# Power_Board_Mk_4.net
KiCad netlist of a schematic drawn in EAGLE
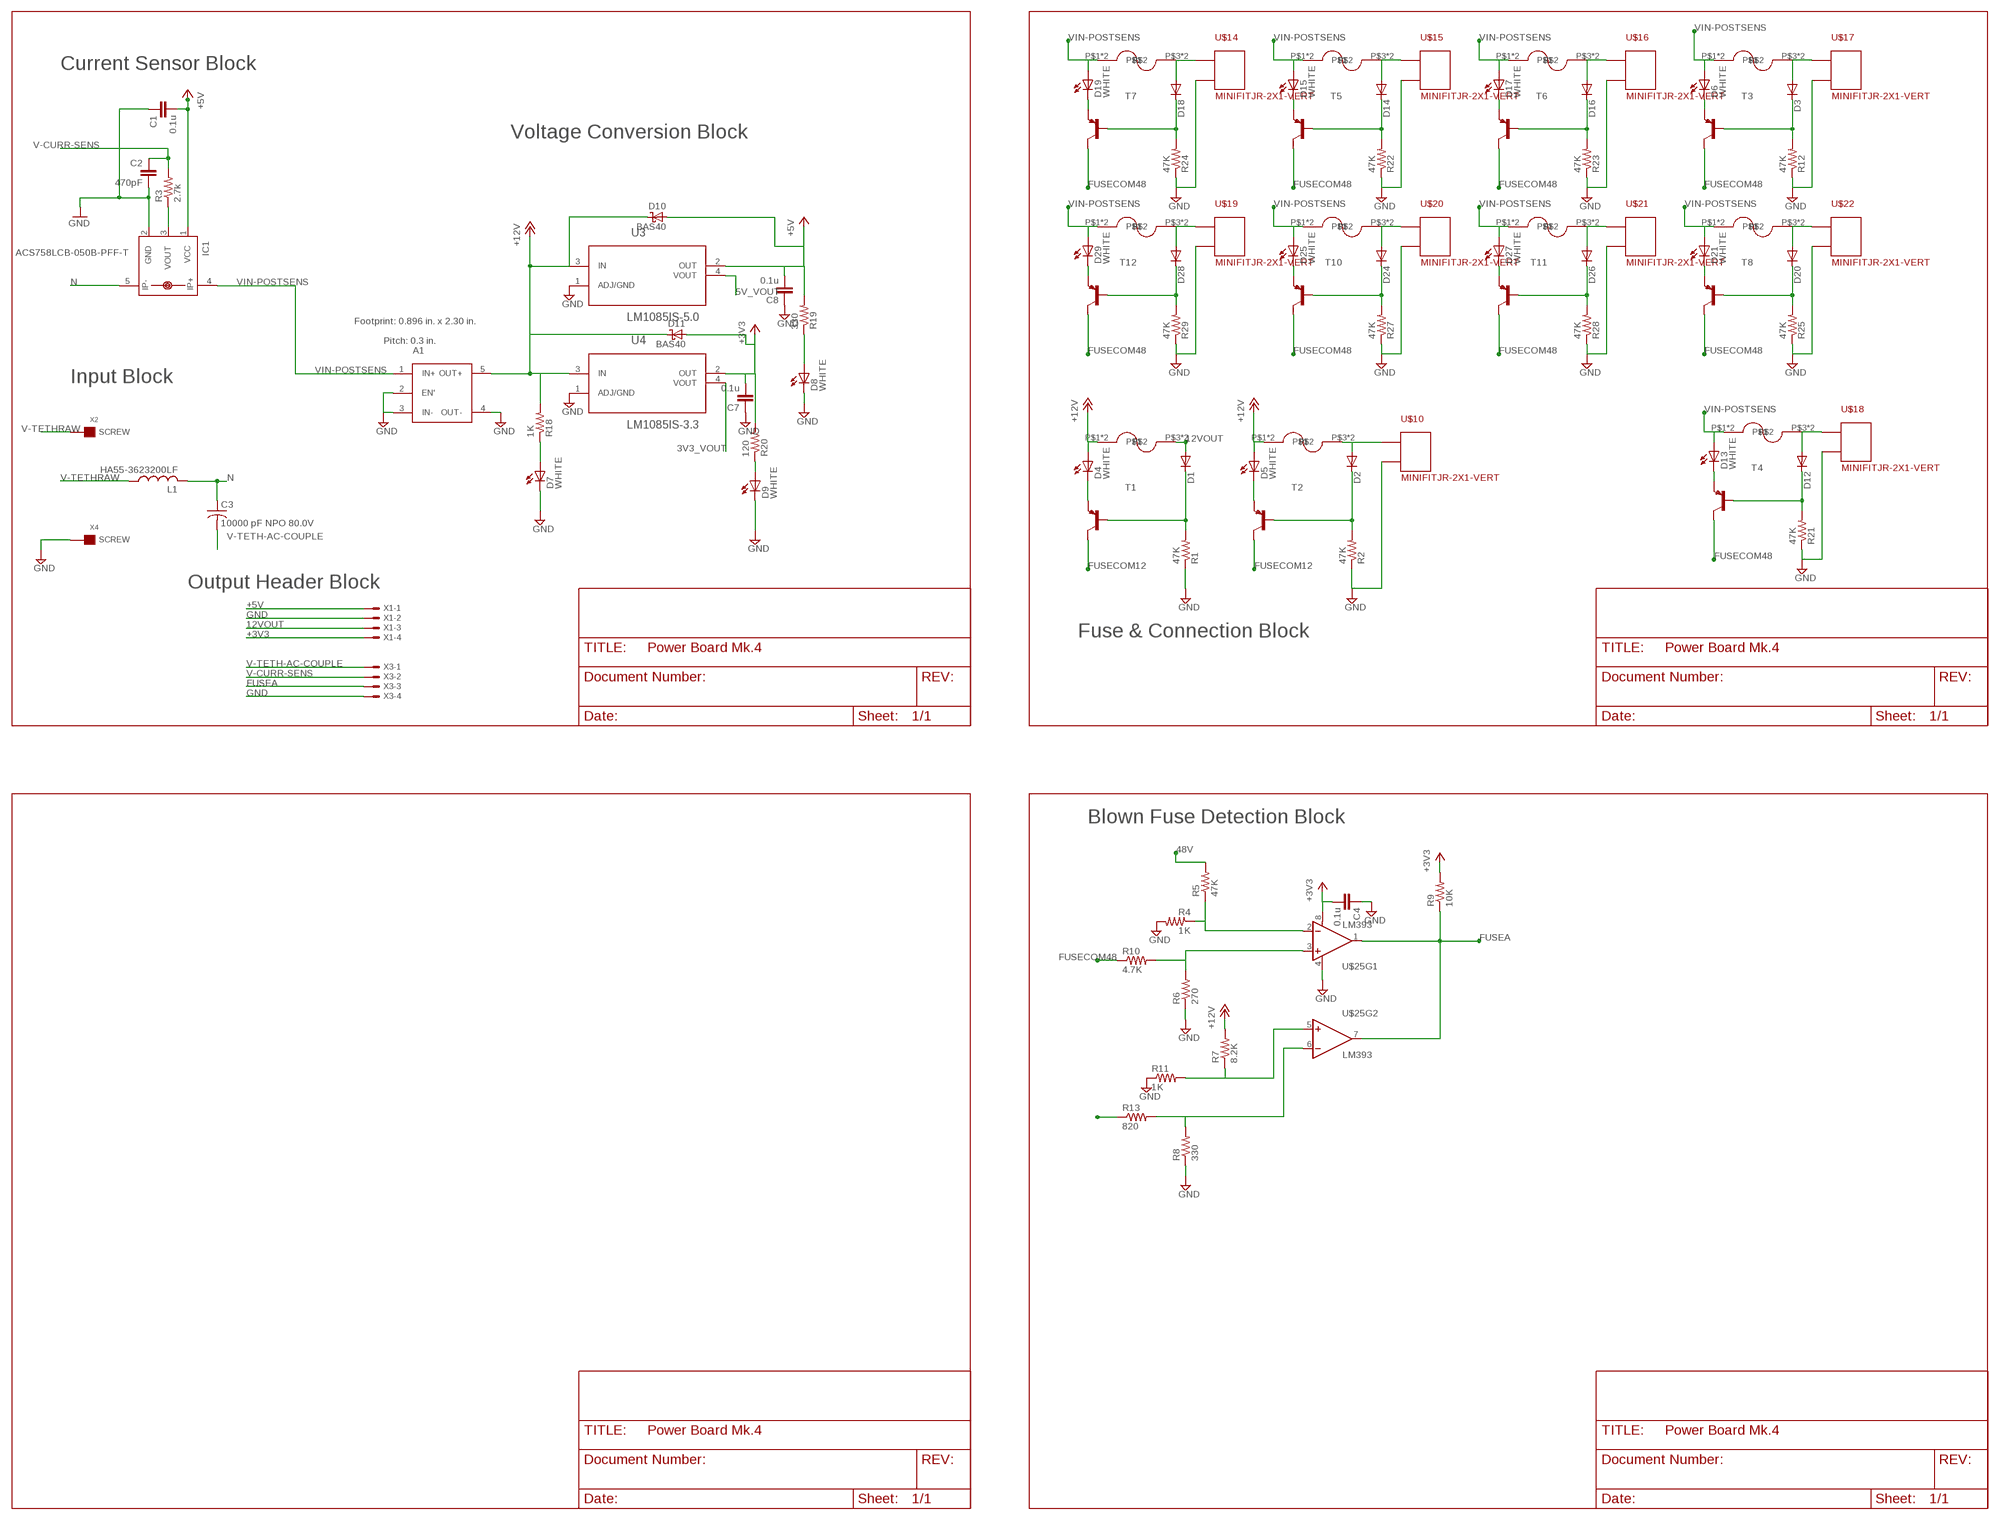
[diagram p0: schematic, sheet 1]

(export (version "E")
  (design (tool "Eeschema 10.0.6"))
  (components
    (comp (ref "A1")
      (value "SQE48T20120")
      (footprint "eagle-import:BRICK")
      (libsource (lib "eagle-import") (part "SQE48T20120"))
    )
    (comp (ref "C1")
      (value "0.1u")
      (footprint "eagle-import:0805")
      (libsource (lib "eagle-import") (part "CAP0805"))
    )
    (comp (ref "C2")
      (value "470pF")
      (footprint "eagle-import:0805")
      (libsource (lib "eagle-import") (part "CAP0805"))
    )
    (comp (ref "C3")
      (value "10000 pF NPO 80.0V")
      (footprint "eagle-import:C0603")
      (libsource (lib "eagle-import") (part "C-USC0603"))
    )
    (comp (ref "C4")
      (value "0.1u")
      (footprint "eagle-import:0805")
      (libsource (lib "eagle-import") (part "CAP0805"))
    )
    (comp (ref "C7")
      (value "0.1u")
      (footprint "eagle-import:0805")
      (libsource (lib "eagle-import") (part "CAP0805"))
    )
    (comp (ref "C8")
      (value "0.1u")
      (footprint "eagle-import:0805")
      (libsource (lib "eagle-import") (part "CAP0805"))
    )
    (comp (ref "D1")
      (value "DIODEHV")
      (footprint "eagle-import:DIODE-HV")
      (libsource (lib "eagle-import") (part "DIODEHV"))
    )
    (comp (ref "D2")
      (value "DIODEHV")
      (footprint "eagle-import:DIODE-HV")
      (libsource (lib "eagle-import") (part "DIODEHV"))
    )
    (comp (ref "D3")
      (value "DIODEHV")
      (footprint "eagle-import:DIODE-HV")
      (libsource (lib "eagle-import") (part "DIODEHV"))
    )
    (comp (ref "D4")
      (value "WHITE")
      (footprint "eagle-import:LED-1206")
      (libsource (lib "eagle-import") (part "LED-WHITE"))
    )
    (comp (ref "D5")
      (value "WHITE")
      (footprint "eagle-import:LED-1206")
      (libsource (lib "eagle-import") (part "LED-WHITE"))
    )
    (comp (ref "D6")
      (value "WHITE")
      (footprint "eagle-import:LED-1206")
      (libsource (lib "eagle-import") (part "LED-WHITE"))
    )
    (comp (ref "D7")
      (value "WHITE")
      (footprint "eagle-import:LED-1206")
      (libsource (lib "eagle-import") (part "LED-WHITE"))
    )
    (comp (ref "D8")
      (value "WHITE")
      (footprint "eagle-import:LED-1206")
      (libsource (lib "eagle-import") (part "LED-WHITE"))
    )
    (comp (ref "D9")
      (value "WHITE")
      (footprint "eagle-import:LED-1206")
      (libsource (lib "eagle-import") (part "LED-WHITE"))
    )
    (comp (ref "D10")
      (value "BAS40")
      (footprint "eagle-import:SOT23")
      (libsource (lib "eagle-import") (part "BAS40"))
    )
    (comp (ref "D11")
      (value "BAS40")
      (footprint "eagle-import:SOT23")
      (libsource (lib "eagle-import") (part "BAS40"))
    )
    (comp (ref "D12")
      (value "DIODEHV")
      (footprint "eagle-import:DIODE-HV")
      (libsource (lib "eagle-import") (part "DIODEHV"))
    )
    (comp (ref "D13")
      (value "WHITE")
      (footprint "eagle-import:LED-1206")
      (libsource (lib "eagle-import") (part "LED-WHITE"))
    )
    (comp (ref "D14")
      (value "DIODEHV")
      (footprint "eagle-import:DIODE-HV")
      (libsource (lib "eagle-import") (part "DIODEHV"))
    )
    (comp (ref "D15")
      (value "WHITE")
      (footprint "eagle-import:LED-1206")
      (libsource (lib "eagle-import") (part "LED-WHITE"))
    )
    (comp (ref "D16")
      (value "DIODEHV")
      (footprint "eagle-import:DIODE-HV")
      (libsource (lib "eagle-import") (part "DIODEHV"))
    )
    (comp (ref "D17")
      (value "WHITE")
      (footprint "eagle-import:LED-1206")
      (libsource (lib "eagle-import") (part "LED-WHITE"))
    )
    (comp (ref "D18")
      (value "DIODEHV")
      (footprint "eagle-import:DIODE-HV")
      (libsource (lib "eagle-import") (part "DIODEHV"))
    )
    (comp (ref "D19")
      (value "WHITE")
      (footprint "eagle-import:LED-1206")
      (libsource (lib "eagle-import") (part "LED-WHITE"))
    )
    (comp (ref "D20")
      (value "DIODEHV")
      (footprint "eagle-import:DIODE-HV")
      (libsource (lib "eagle-import") (part "DIODEHV"))
    )
    (comp (ref "D21")
      (value "WHITE")
      (footprint "eagle-import:LED-1206")
      (libsource (lib "eagle-import") (part "LED-WHITE"))
    )
    (comp (ref "D24")
      (value "DIODEHV")
      (footprint "eagle-import:DIODE-HV")
      (libsource (lib "eagle-import") (part "DIODEHV"))
    )
    (comp (ref "D25")
      (value "WHITE")
      (footprint "eagle-import:LED-1206")
      (libsource (lib "eagle-import") (part "LED-WHITE"))
    )
    (comp (ref "D26")
      (value "DIODEHV")
      (footprint "eagle-import:DIODE-HV")
      (libsource (lib "eagle-import") (part "DIODEHV"))
    )
    (comp (ref "D27")
      (value "WHITE")
      (footprint "eagle-import:LED-1206")
      (libsource (lib "eagle-import") (part "LED-WHITE"))
    )
    (comp (ref "D28")
      (value "DIODEHV")
      (footprint "eagle-import:DIODE-HV")
      (libsource (lib "eagle-import") (part "DIODEHV"))
    )
    (comp (ref "D29")
      (value "WHITE")
      (footprint "eagle-import:LED-1206")
      (libsource (lib "eagle-import") (part "LED-WHITE"))
    )
    (comp (ref "IC1")
      (value "ACS758LCB-050B-PFF-T")
      (footprint "eagle-import:CB-PFF")
      (libsource (lib "eagle-import") (part "ACS758LCB-050B-PFF-T"))
    )
    (comp (ref "L1")
      (value "HA55-3623200LF")
      (footprint "eagle-import:THIND")
      (libsource (lib "eagle-import") (part "HA55-3623200LF"))
    )
    (comp (ref "R1")
      (value "47K")
      (footprint "eagle-import:0805")
      (libsource (lib "eagle-import") (part "RESISTOR0805-RES"))
    )
    (comp (ref "R2")
      (value "47K")
      (footprint "eagle-import:0805")
      (libsource (lib "eagle-import") (part "RESISTOR0805-RES"))
    )
    (comp (ref "R3")
      (value "2.7k")
      (footprint "eagle-import:0805")
      (libsource (lib "eagle-import") (part "RESISTOR0805-RES"))
    )
    (comp (ref "R4")
      (value "1K")
      (footprint "eagle-import:0805")
      (libsource (lib "eagle-import") (part "RESISTOR0805-RES"))
    )
    (comp (ref "R5")
      (value "47K")
      (footprint "eagle-import:0805")
      (libsource (lib "eagle-import") (part "RESISTOR0805-RES"))
    )
    (comp (ref "R6")
      (value "270")
      (footprint "eagle-import:0805")
      (libsource (lib "eagle-import") (part "RESISTOR0805-RES"))
    )
    (comp (ref "R7")
      (value "8.2K")
      (footprint "eagle-import:0805")
      (libsource (lib "eagle-import") (part "RESISTOR0805-RES"))
    )
    (comp (ref "R8")
      (value "330")
      (footprint "eagle-import:0805")
      (libsource (lib "eagle-import") (part "RESISTOR0805-RES"))
    )
    (comp (ref "R9")
      (value "10K")
      (footprint "eagle-import:0805")
      (libsource (lib "eagle-import") (part "RESISTOR0805-RES"))
    )
    (comp (ref "R10")
      (value "4.7K")
      (footprint "eagle-import:0805")
      (libsource (lib "eagle-import") (part "RESISTOR0805-RES"))
    )
    (comp (ref "R11")
      (value "1K")
      (footprint "eagle-import:0805")
      (libsource (lib "eagle-import") (part "RESISTOR0805-RES"))
    )
    (comp (ref "R12")
      (value "47K")
      (footprint "eagle-import:0805")
      (libsource (lib "eagle-import") (part "RESISTOR0805-RES"))
    )
    (comp (ref "R13")
      (value "820")
      (footprint "eagle-import:0805")
      (libsource (lib "eagle-import") (part "RESISTOR0805-RES"))
    )
    (comp (ref "R18")
      (value "1K")
      (footprint "eagle-import:0805")
      (libsource (lib "eagle-import") (part "RESISTOR0805-RES"))
    )
    (comp (ref "R19")
      (value "330")
      (footprint "eagle-import:0805")
      (libsource (lib "eagle-import") (part "RESISTOR0805-RES"))
    )
    (comp (ref "R20")
      (value "120")
      (footprint "eagle-import:0805")
      (libsource (lib "eagle-import") (part "RESISTOR0805-RES"))
    )
    (comp (ref "R21")
      (value "47K")
      (footprint "eagle-import:0805")
      (libsource (lib "eagle-import") (part "RESISTOR0805-RES"))
    )
    (comp (ref "R22")
      (value "47K")
      (footprint "eagle-import:0805")
      (libsource (lib "eagle-import") (part "RESISTOR0805-RES"))
    )
    (comp (ref "R23")
      (value "47K")
      (footprint "eagle-import:0805")
      (libsource (lib "eagle-import") (part "RESISTOR0805-RES"))
    )
    (comp (ref "R24")
      (value "47K")
      (footprint "eagle-import:0805")
      (libsource (lib "eagle-import") (part "RESISTOR0805-RES"))
    )
    (comp (ref "R25")
      (value "47K")
      (footprint "eagle-import:0805")
      (libsource (lib "eagle-import") (part "RESISTOR0805-RES"))
    )
    (comp (ref "R27")
      (value "47K")
      (footprint "eagle-import:0805")
      (libsource (lib "eagle-import") (part "RESISTOR0805-RES"))
    )
    (comp (ref "R28")
      (value "47K")
      (footprint "eagle-import:0805")
      (libsource (lib "eagle-import") (part "RESISTOR0805-RES"))
    )
    (comp (ref "R29")
      (value "47K")
      (footprint "eagle-import:0805")
      (libsource (lib "eagle-import") (part "RESISTOR0805-RES"))
    )
    (comp (ref "T1")
      (value "BC856BLT1-PNP-SOT23-BEC")
      (footprint "eagle-import:SOT23-BEC")
      (libsource (lib "eagle-import") (part "-PNP-SOT23-BECBC856BLT1"))
    )
    (comp (ref "T2")
      (value "BC856BLT1-PNP-SOT23-BEC")
      (footprint "eagle-import:SOT23-BEC")
      (libsource (lib "eagle-import") (part "-PNP-SOT23-BECBC856BLT1"))
    )
    (comp (ref "T3")
      (value "BC856BLT1-PNP-SOT23-BEC")
      (footprint "eagle-import:SOT23-BEC")
      (libsource (lib "eagle-import") (part "-PNP-SOT23-BECBC856BLT1"))
    )
    (comp (ref "T4")
      (value "BC856BLT1-PNP-SOT23-BEC")
      (footprint "eagle-import:SOT23-BEC")
      (libsource (lib "eagle-import") (part "-PNP-SOT23-BECBC856BLT1"))
    )
    (comp (ref "T5")
      (value "BC856BLT1-PNP-SOT23-BEC")
      (footprint "eagle-import:SOT23-BEC")
      (libsource (lib "eagle-import") (part "-PNP-SOT23-BECBC856BLT1"))
    )
    (comp (ref "T6")
      (value "BC856BLT1-PNP-SOT23-BEC")
      (footprint "eagle-import:SOT23-BEC")
      (libsource (lib "eagle-import") (part "-PNP-SOT23-BECBC856BLT1"))
    )
    (comp (ref "T7")
      (value "BC856BLT1-PNP-SOT23-BEC")
      (footprint "eagle-import:SOT23-BEC")
      (libsource (lib "eagle-import") (part "-PNP-SOT23-BECBC856BLT1"))
    )
    (comp (ref "T8")
      (value "BC856BLT1-PNP-SOT23-BEC")
      (footprint "eagle-import:SOT23-BEC")
      (libsource (lib "eagle-import") (part "-PNP-SOT23-BECBC856BLT1"))
    )
    (comp (ref "T10")
      (value "BC856BLT1-PNP-SOT23-BEC")
      (footprint "eagle-import:SOT23-BEC")
      (libsource (lib "eagle-import") (part "-PNP-SOT23-BECBC856BLT1"))
    )
    (comp (ref "T11")
      (value "BC856BLT1-PNP-SOT23-BEC")
      (footprint "eagle-import:SOT23-BEC")
      (libsource (lib "eagle-import") (part "-PNP-SOT23-BECBC856BLT1"))
    )
    (comp (ref "T12")
      (value "BC856BLT1-PNP-SOT23-BEC")
      (footprint "eagle-import:SOT23-BEC")
      (libsource (lib "eagle-import") (part "-PNP-SOT23-BECBC856BLT1"))
    )
    (comp (ref "U$2")
      (value "FUSEHOLDER3557-2")
      (footprint "eagle-import:FUSEHOLDER3557-2")
      (libsource (lib "eagle-import") (part "FUSEHOLDER3557-2"))
    )
    (comp (ref "U$3")
      (value "FUSEHOLDER3557-2")
      (footprint "eagle-import:FUSEHOLDER3557-2")
      (libsource (lib "eagle-import") (part "FUSEHOLDER3557-2"))
    )
    (comp (ref "U$4")
      (value "FUSEHOLDER3557-2")
      (footprint "eagle-import:FUSEHOLDER3557-2")
      (libsource (lib "eagle-import") (part "FUSEHOLDER3557-2"))
    )
    (comp (ref "U$5")
      (value "FUSEHOLDER3557-2")
      (footprint "eagle-import:FUSEHOLDER3557-2")
      (libsource (lib "eagle-import") (part "FUSEHOLDER3557-2"))
    )
    (comp (ref "U$6")
      (value "FUSEHOLDER3557-2")
      (footprint "eagle-import:FUSEHOLDER3557-2")
      (libsource (lib "eagle-import") (part "FUSEHOLDER3557-2"))
    )
    (comp (ref "U$7")
      (value "FUSEHOLDER3557-2")
      (footprint "eagle-import:FUSEHOLDER3557-2")
      (libsource (lib "eagle-import") (part "FUSEHOLDER3557-2"))
    )
    (comp (ref "U$8")
      (value "FUSEHOLDER3557-2")
      (footprint "eagle-import:FUSEHOLDER3557-2")
      (libsource (lib "eagle-import") (part "FUSEHOLDER3557-2"))
    )
    (comp (ref "U$9")
      (value "FUSEHOLDER3557-2")
      (footprint "eagle-import:FUSEHOLDER3557-2")
      (libsource (lib "eagle-import") (part "FUSEHOLDER3557-2"))
    )
    (comp (ref "U$10")
      (value "MINIFITJR-2X1-VERT")
      (footprint "eagle-import:5566-02B")
      (libsource (lib "eagle-import") (part "MINIFITJR-2X1-VERT"))
    )
    (comp (ref "U$11")
      (value "FUSEHOLDER3557-2")
      (footprint "eagle-import:FUSEHOLDER3557-2")
      (libsource (lib "eagle-import") (part "FUSEHOLDER3557-2"))
    )
    (comp (ref "U$12")
      (value "FUSEHOLDER3557-2")
      (footprint "eagle-import:FUSEHOLDER3557-2")
      (libsource (lib "eagle-import") (part "FUSEHOLDER3557-2"))
    )
    (comp (ref "U$13")
      (value "FUSEHOLDER3557-2")
      (footprint "eagle-import:FUSEHOLDER3557-2")
      (libsource (lib "eagle-import") (part "FUSEHOLDER3557-2"))
    )
    (comp (ref "U$14")
      (value "MINIFITJR-2X1-VERT")
      (footprint "eagle-import:5566-02B")
      (libsource (lib "eagle-import") (part "MINIFITJR-2X1-VERT"))
    )
    (comp (ref "U$15")
      (value "MINIFITJR-2X1-VERT")
      (footprint "eagle-import:5566-02B")
      (libsource (lib "eagle-import") (part "MINIFITJR-2X1-VERT"))
    )
    (comp (ref "U$16")
      (value "MINIFITJR-2X1-VERT")
      (footprint "eagle-import:5566-02B")
      (libsource (lib "eagle-import") (part "MINIFITJR-2X1-VERT"))
    )
    (comp (ref "U$17")
      (value "MINIFITJR-2X1-VERT")
      (footprint "eagle-import:5566-02B")
      (libsource (lib "eagle-import") (part "MINIFITJR-2X1-VERT"))
    )
    (comp (ref "U$18")
      (value "MINIFITJR-2X1-VERT")
      (footprint "eagle-import:5566-02B")
      (libsource (lib "eagle-import") (part "MINIFITJR-2X1-VERT"))
    )
    (comp (ref "U$19")
      (value "MINIFITJR-2X1-VERT")
      (footprint "eagle-import:5566-02B")
      (libsource (lib "eagle-import") (part "MINIFITJR-2X1-VERT"))
    )
    (comp (ref "U$20")
      (value "MINIFITJR-2X1-VERT")
      (footprint "eagle-import:5566-02B")
      (libsource (lib "eagle-import") (part "MINIFITJR-2X1-VERT"))
    )
    (comp (ref "U$21")
      (value "MINIFITJR-2X1-VERT")
      (footprint "eagle-import:5566-02B")
      (libsource (lib "eagle-import") (part "MINIFITJR-2X1-VERT"))
    )
    (comp (ref "U$22")
      (value "MINIFITJR-2X1-VERT")
      (footprint "eagle-import:5566-02B")
      (libsource (lib "eagle-import") (part "MINIFITJR-2X1-VERT"))
    )
    (comp (ref "U$25")
      (value "LM393")
      (footprint "eagle-import:SO08")
      (libsource (lib "eagle-import") (part "LM393"))
    )
    (comp (ref "U3")
      (value "LM1085IS-5.0")
      (footprint "eagle-import:TO254P1435X457-3N")
      (libsource (lib "eagle-import") (part "LM1085IS-5.0"))
    )
    (comp (ref "U4")
      (value "LM1085IS-3.3")
      (footprint "eagle-import:TO254P1435X457-3N")
      (libsource (lib "eagle-import") (part "LM1085IS-3.3"))
    )
    (comp (ref "X1")
      (value "KK-156-4")
      (footprint "eagle-import:KK-156-4")
      (libsource (lib "eagle-import") (part "KK-156-4"))
    )
    (comp (ref "X2")
      (value "SCREW_TERM")
      (footprint "eagle-import:TERMINAL")
      (libsource (lib "eagle-import") (part "SCREW_TERM"))
    )
    (comp (ref "X3")
      (value "KK-156-4")
      (footprint "eagle-import:KK-156-4")
      (libsource (lib "eagle-import") (part "KK-156-4"))
    )
    (comp (ref "X4")
      (value "SCREW_TERM")
      (footprint "eagle-import:TERMINAL")
      (libsource (lib "eagle-import") (part "SCREW_TERM"))
    )
  )
  (nets
    (net (code "1") (name "+3V3") (class "Default")
      (node (ref "C4") (pin "2") (pinfunction "2_2") (pintype "passive"))
      (node (ref "C7") (pin "2") (pinfunction "2_2") (pintype "passive"))
      (node (ref "D11") (pin "1") (pinfunction "A_1") (pintype "passive"))
      (node (ref "R20") (pin "2") (pinfunction "2_2") (pintype "passive"))
      (node (ref "R9") (pin "2") (pinfunction "2_2") (pintype "passive"))
      (node (ref "U$25") (pin "8") (pinfunction "V+_8") (pintype "power_in"))
      (node (ref "U4") (pin "2") (pinfunction "OUT_2") (pintype "output"))
      (node (ref "X1") (pin "4") (pinfunction "S_4") (pintype "passive"))
    )
    (net (code "2") (name "+5V") (class "Default")
      (node (ref "C1") (pin "2") (pinfunction "2_2") (pintype "passive"))
      (node (ref "C8") (pin "2") (pinfunction "2_2") (pintype "passive"))
      (node (ref "D10") (pin "1") (pinfunction "A_1") (pintype "passive"))
      (node (ref "IC1") (pin "1") (pinfunction "VCC_1") (pintype "power_in"))
      (node (ref "R19") (pin "2") (pinfunction "2_2") (pintype "passive"))
      (node (ref "U3") (pin "2") (pinfunction "OUT_2") (pintype "output"))
      (node (ref "X1") (pin "1") (pinfunction "S_1") (pintype "passive"))
    )
    (net (code "3") (name "+12V") (class "Default")
      (node (ref "A1") (pin "5") (pinfunction "OUT+_5") (pintype "bidirectional"))
      (node (ref "D10") (pin "3") (pinfunction "C_3") (pintype "passive"))
      (node (ref "D11") (pin "3") (pinfunction "C_3") (pintype "passive"))
      (node (ref "D4") (pin "A") (pinfunction "A_A") (pintype "passive"))
      (node (ref "D5") (pin "A") (pinfunction "A_A") (pintype "passive"))
      (node (ref "R18") (pin "2") (pinfunction "2_2") (pintype "passive"))
      (node (ref "R7") (pin "2") (pinfunction "2_2") (pintype "passive"))
      (node (ref "U$3") (pin "P$1") (pinfunction "P$1_P$1") (pintype "bidirectional"))
      (node (ref "U$3") (pin "P$2") (pinfunction "P$1_P$2") (pintype "bidirectional"))
      (node (ref "U$4") (pin "P$1") (pinfunction "P$1_P$1") (pintype "bidirectional"))
      (node (ref "U$4") (pin "P$2") (pinfunction "P$1_P$2") (pintype "bidirectional"))
      (node (ref "U3") (pin "3") (pinfunction "IN_3") (pintype "power_in"))
      (node (ref "U4") (pin "3") (pinfunction "IN_3") (pintype "power_in"))
    )
    (net (code "4") (name "/3V3_VOUT") (class "Default")
      (node (ref "U4") (pin "4") (pinfunction "VOUT_4") (pintype "output"))
    )
    (net (code "5") (name "/5V_VOUT") (class "Default")
      (node (ref "U3") (pin "4") (pinfunction "VOUT_4") (pintype "output"))
    )
    (net (code "6") (name "/12VOUT") (class "Default")
      (node (ref "D1") (pin "A") (pinfunction "A_A") (pintype "passive"))
      (node (ref "U$4") (pin "P$3") (pinfunction "P$2_P$3") (pintype "bidirectional"))
      (node (ref "U$4") (pin "P$4") (pinfunction "P$2_P$4") (pintype "bidirectional"))
      (node (ref "X1") (pin "3") (pinfunction "S_3") (pintype "passive"))
    )
    (net (code "7") (name "/48V") (class "Default")
      (node (ref "R5") (pin "2") (pinfunction "2_2") (pintype "passive"))
    )
    (net (code "8") (name "/FUSEA") (class "Default")
      (node (ref "R9") (pin "1") (pinfunction "1_1") (pintype "passive"))
      (node (ref "U$25") (pin "1") (pinfunction "OUT_1") (pintype "output"))
      (node (ref "U$25") (pin "7") (pinfunction "OUT_7") (pintype "output"))
      (node (ref "X3") (pin "3") (pinfunction "S_3") (pintype "passive"))
    )
    (net (code "9") (name "/FUSECOM12") (class "Default")
      (node (ref "R13") (pin "1") (pinfunction "1_1") (pintype "passive"))
      (node (ref "T1") (pin "C") (pinfunction "C_C") (pintype "passive"))
      (node (ref "T2") (pin "C") (pinfunction "C_C") (pintype "passive"))
    )
    (net (code "10") (name "/FUSECOM48") (class "Default")
      (node (ref "R10") (pin "1") (pinfunction "1_1") (pintype "passive"))
      (node (ref "T10") (pin "C") (pinfunction "C_C") (pintype "passive"))
      (node (ref "T11") (pin "C") (pinfunction "C_C") (pintype "passive"))
      (node (ref "T12") (pin "C") (pinfunction "C_C") (pintype "passive"))
      (node (ref "T3") (pin "C") (pinfunction "C_C") (pintype "passive"))
      (node (ref "T4") (pin "C") (pinfunction "C_C") (pintype "passive"))
      (node (ref "T5") (pin "C") (pinfunction "C_C") (pintype "passive"))
      (node (ref "T6") (pin "C") (pinfunction "C_C") (pintype "passive"))
      (node (ref "T7") (pin "C") (pinfunction "C_C") (pintype "passive"))
      (node (ref "T8") (pin "C") (pinfunction "C_C") (pintype "passive"))
    )
    (net (code "11") (name "/N") (class "Default")
      (node (ref "C3") (pin "1") (pinfunction "1_1") (pintype "passive"))
      (node (ref "IC1") (pin "5") (pinfunction "IP-_5") (pintype "passive"))
      (node (ref "L1") (pin "2") (pinfunction "2_2") (pintype "passive"))
    )
    (net (code "12") (name "/V-CURR-SENS") (class "Default")
      (node (ref "C2") (pin "1") (pinfunction "1_1") (pintype "passive"))
      (node (ref "R3") (pin "2") (pinfunction "2_2") (pintype "passive"))
      (node (ref "X3") (pin "2") (pinfunction "S_2") (pintype "passive"))
    )
    (net (code "13") (name "/V-TETH-AC-COUPLE") (class "Default")
      (node (ref "C3") (pin "2") (pinfunction "2_2") (pintype "passive"))
      (node (ref "X3") (pin "1") (pinfunction "S_1") (pintype "passive"))
    )
    (net (code "14") (name "/V-TETHRAW") (class "Default")
      (node (ref "L1") (pin "1") (pinfunction "1_1") (pintype "passive"))
      (node (ref "X2") (pin "P$1") (pinfunction "SCREW_P$1") (pintype "bidirectional"))
      (node (ref "X2") (pin "P$10") (pinfunction "SCREW_P$10") (pintype "bidirectional"))
      (node (ref "X2") (pin "P$2") (pinfunction "SCREW_P$2") (pintype "bidirectional"))
      (node (ref "X2") (pin "P$3") (pinfunction "SCREW_P$3") (pintype "bidirectional"))
      (node (ref "X2") (pin "P$4") (pinfunction "SCREW_P$4") (pintype "bidirectional"))
      (node (ref "X2") (pin "P$5") (pinfunction "SCREW_P$5") (pintype "bidirectional"))
      (node (ref "X2") (pin "P$6") (pinfunction "SCREW_P$6") (pintype "bidirectional"))
      (node (ref "X2") (pin "P$7") (pinfunction "SCREW_P$7") (pintype "bidirectional"))
      (node (ref "X2") (pin "P$8") (pinfunction "SCREW_P$8") (pintype "bidirectional"))
      (node (ref "X2") (pin "P$9") (pinfunction "SCREW_P$9") (pintype "bidirectional"))
    )
    (net (code "15") (name "/VIN-POSTSENS") (class "Default")
      (node (ref "A1") (pin "1") (pinfunction "IN+_1") (pintype "bidirectional"))
      (node (ref "D13") (pin "A") (pinfunction "A_A") (pintype "passive"))
      (node (ref "D15") (pin "A") (pinfunction "A_A") (pintype "passive"))
      (node (ref "D17") (pin "A") (pinfunction "A_A") (pintype "passive"))
      (node (ref "D19") (pin "A") (pinfunction "A_A") (pintype "passive"))
      (node (ref "D21") (pin "A") (pinfunction "A_A") (pintype "passive"))
      (node (ref "D25") (pin "A") (pinfunction "A_A") (pintype "passive"))
      (node (ref "D27") (pin "A") (pinfunction "A_A") (pintype "passive"))
      (node (ref "D29") (pin "A") (pinfunction "A_A") (pintype "passive"))
      (node (ref "D6") (pin "A") (pinfunction "A_A") (pintype "passive"))
      (node (ref "IC1") (pin "4") (pinfunction "IP+_4") (pintype "passive"))
      (node (ref "U$11") (pin "P$1") (pinfunction "P$1_P$1") (pintype "bidirectional"))
      (node (ref "U$11") (pin "P$2") (pinfunction "P$1_P$2") (pintype "bidirectional"))
      (node (ref "U$12") (pin "P$1") (pinfunction "P$1_P$1") (pintype "bidirectional"))
      (node (ref "U$12") (pin "P$2") (pinfunction "P$1_P$2") (pintype "bidirectional"))
      (node (ref "U$13") (pin "P$1") (pinfunction "P$1_P$1") (pintype "bidirectional"))
      (node (ref "U$13") (pin "P$2") (pinfunction "P$1_P$2") (pintype "bidirectional"))
      (node (ref "U$2") (pin "P$1") (pinfunction "P$1_P$1") (pintype "bidirectional"))
      (node (ref "U$2") (pin "P$2") (pinfunction "P$1_P$2") (pintype "bidirectional"))
      (node (ref "U$5") (pin "P$1") (pinfunction "P$1_P$1") (pintype "bidirectional"))
      (node (ref "U$5") (pin "P$2") (pinfunction "P$1_P$2") (pintype "bidirectional"))
      (node (ref "U$6") (pin "P$1") (pinfunction "P$1_P$1") (pintype "bidirectional"))
      (node (ref "U$6") (pin "P$2") (pinfunction "P$1_P$2") (pintype "bidirectional"))
      (node (ref "U$7") (pin "P$1") (pinfunction "P$1_P$1") (pintype "bidirectional"))
      (node (ref "U$7") (pin "P$2") (pinfunction "P$1_P$2") (pintype "bidirectional"))
      (node (ref "U$8") (pin "P$1") (pinfunction "P$1_P$1") (pintype "bidirectional"))
      (node (ref "U$8") (pin "P$2") (pinfunction "P$1_P$2") (pintype "bidirectional"))
      (node (ref "U$9") (pin "P$1") (pinfunction "P$1_P$1") (pintype "bidirectional"))
      (node (ref "U$9") (pin "P$2") (pinfunction "P$1_P$2") (pintype "bidirectional"))
    )
    (net (code "16") (name "GND") (class "Default")
      (node (ref "A1") (pin "2") (pinfunction "EN'_2") (pintype "bidirectional"))
      (node (ref "A1") (pin "3") (pinfunction "IN-_3") (pintype "bidirectional"))
      (node (ref "A1") (pin "4") (pinfunction "OUT-_4") (pintype "bidirectional"))
      (node (ref "C1") (pin "1") (pinfunction "1_1") (pintype "passive"))
      (node (ref "C2") (pin "2") (pinfunction "2_2") (pintype "passive"))
      (node (ref "C4") (pin "1") (pinfunction "1_1") (pintype "passive"))
      (node (ref "C7") (pin "1") (pinfunction "1_1") (pintype "passive"))
      (node (ref "C8") (pin "1") (pinfunction "1_1") (pintype "passive"))
      (node (ref "D7") (pin "C") (pinfunction "C_C") (pintype "passive"))
      (node (ref "D8") (pin "C") (pinfunction "C_C") (pintype "passive"))
      (node (ref "D9") (pin "C") (pinfunction "C_C") (pintype "passive"))
      (node (ref "IC1") (pin "2") (pinfunction "GND_2") (pintype "power_in"))
      (node (ref "R1") (pin "1") (pinfunction "1_1") (pintype "passive"))
      (node (ref "R11") (pin "1") (pinfunction "1_1") (pintype "passive"))
      (node (ref "R12") (pin "1") (pinfunction "1_1") (pintype "passive"))
      (node (ref "R2") (pin "1") (pinfunction "1_1") (pintype "passive"))
      (node (ref "R21") (pin "1") (pinfunction "1_1") (pintype "passive"))
      (node (ref "R22") (pin "1") (pinfunction "1_1") (pintype "passive"))
      (node (ref "R23") (pin "1") (pinfunction "1_1") (pintype "passive"))
      (node (ref "R24") (pin "1") (pinfunction "1_1") (pintype "passive"))
      (node (ref "R25") (pin "1") (pinfunction "1_1") (pintype "passive"))
      (node (ref "R27") (pin "1") (pinfunction "1_1") (pintype "passive"))
      (node (ref "R28") (pin "1") (pinfunction "1_1") (pintype "passive"))
      (node (ref "R29") (pin "1") (pinfunction "1_1") (pintype "passive"))
      (node (ref "R4") (pin "2") (pinfunction "2_2") (pintype "passive"))
      (node (ref "R6") (pin "1") (pinfunction "1_1") (pintype "passive"))
      (node (ref "R8") (pin "1") (pinfunction "1_1") (pintype "passive"))
      (node (ref "U$10") (pin "P$2") (pinfunction "P$2_P$2") (pintype "bidirectional"))
      (node (ref "U$14") (pin "P$2") (pinfunction "P$2_P$2") (pintype "bidirectional"))
      (node (ref "U$15") (pin "P$2") (pinfunction "P$2_P$2") (pintype "bidirectional"))
      (node (ref "U$16") (pin "P$2") (pinfunction "P$2_P$2") (pintype "bidirectional"))
      (node (ref "U$17") (pin "P$2") (pinfunction "P$2_P$2") (pintype "bidirectional"))
      (node (ref "U$18") (pin "P$2") (pinfunction "P$2_P$2") (pintype "bidirectional"))
      (node (ref "U$19") (pin "P$2") (pinfunction "P$2_P$2") (pintype "bidirectional"))
      (node (ref "U$20") (pin "P$2") (pinfunction "P$2_P$2") (pintype "bidirectional"))
      (node (ref "U$21") (pin "P$2") (pinfunction "P$2_P$2") (pintype "bidirectional"))
      (node (ref "U$22") (pin "P$2") (pinfunction "P$2_P$2") (pintype "bidirectional"))
      (node (ref "U$25") (pin "4") (pinfunction "V-_4") (pintype "power_in"))
      (node (ref "U3") (pin "1") (pinfunction "ADJ/GND_1") (pintype "passive"))
      (node (ref "U4") (pin "1") (pinfunction "ADJ/GND_1") (pintype "passive"))
      (node (ref "X1") (pin "2") (pinfunction "S_2") (pintype "passive"))
      (node (ref "X3") (pin "4") (pinfunction "S_4") (pintype "passive"))
      (node (ref "X4") (pin "P$1") (pinfunction "SCREW_P$1") (pintype "bidirectional"))
      (node (ref "X4") (pin "P$10") (pinfunction "SCREW_P$10") (pintype "bidirectional"))
      (node (ref "X4") (pin "P$2") (pinfunction "SCREW_P$2") (pintype "bidirectional"))
      (node (ref "X4") (pin "P$3") (pinfunction "SCREW_P$3") (pintype "bidirectional"))
      (node (ref "X4") (pin "P$4") (pinfunction "SCREW_P$4") (pintype "bidirectional"))
      (node (ref "X4") (pin "P$5") (pinfunction "SCREW_P$5") (pintype "bidirectional"))
      (node (ref "X4") (pin "P$6") (pinfunction "SCREW_P$6") (pintype "bidirectional"))
      (node (ref "X4") (pin "P$7") (pinfunction "SCREW_P$7") (pintype "bidirectional"))
      (node (ref "X4") (pin "P$8") (pinfunction "SCREW_P$8") (pintype "bidirectional"))
      (node (ref "X4") (pin "P$9") (pinfunction "SCREW_P$9") (pintype "bidirectional"))
    )
    (net (code "17") (name "Net-(D1-PadC)") (class "Default")
      (node (ref "D1") (pin "C") (pinfunction "C_C") (pintype "passive"))
      (node (ref "R1") (pin "2") (pinfunction "2_2") (pintype "passive"))
      (node (ref "T1") (pin "B") (pinfunction "B_B") (pintype "passive"))
    )
    (net (code "18") (name "Net-(D2-PadA)") (class "Default")
      (node (ref "D2") (pin "A") (pinfunction "A_A") (pintype "passive"))
      (node (ref "U$10") (pin "P$1") (pinfunction "P$1_P$1") (pintype "bidirectional"))
      (node (ref "U$3") (pin "P$3") (pinfunction "P$2_P$3") (pintype "bidirectional"))
      (node (ref "U$3") (pin "P$4") (pinfunction "P$2_P$4") (pintype "bidirectional"))
    )
    (net (code "19") (name "Net-(D2-PadC)") (class "Default")
      (node (ref "D2") (pin "C") (pinfunction "C_C") (pintype "passive"))
      (node (ref "R2") (pin "2") (pinfunction "2_2") (pintype "passive"))
      (node (ref "T2") (pin "B") (pinfunction "B_B") (pintype "passive"))
    )
    (net (code "20") (name "Net-(D3-PadA)") (class "Default")
      (node (ref "D3") (pin "A") (pinfunction "A_A") (pintype "passive"))
      (node (ref "U$17") (pin "P$1") (pinfunction "P$1_P$1") (pintype "bidirectional"))
      (node (ref "U$2") (pin "P$3") (pinfunction "P$2_P$3") (pintype "bidirectional"))
      (node (ref "U$2") (pin "P$4") (pinfunction "P$2_P$4") (pintype "bidirectional"))
    )
    (net (code "21") (name "Net-(D3-PadC)") (class "Default")
      (node (ref "D3") (pin "C") (pinfunction "C_C") (pintype "passive"))
      (node (ref "R12") (pin "2") (pinfunction "2_2") (pintype "passive"))
      (node (ref "T3") (pin "B") (pinfunction "B_B") (pintype "passive"))
    )
    (net (code "22") (name "Net-(D4-PadC)") (class "Default")
      (node (ref "D4") (pin "C") (pinfunction "C_C") (pintype "passive"))
      (node (ref "T1") (pin "E") (pinfunction "E_E") (pintype "passive"))
    )
    (net (code "23") (name "Net-(D5-PadC)") (class "Default")
      (node (ref "D5") (pin "C") (pinfunction "C_C") (pintype "passive"))
      (node (ref "T2") (pin "E") (pinfunction "E_E") (pintype "passive"))
    )
    (net (code "24") (name "Net-(D6-PadC)") (class "Default")
      (node (ref "D6") (pin "C") (pinfunction "C_C") (pintype "passive"))
      (node (ref "T3") (pin "E") (pinfunction "E_E") (pintype "passive"))
    )
    (net (code "25") (name "Net-(D7-PadA)") (class "Default")
      (node (ref "D7") (pin "A") (pinfunction "A_A") (pintype "passive"))
      (node (ref "R18") (pin "1") (pinfunction "1_1") (pintype "passive"))
    )
    (net (code "26") (name "Net-(D8-PadA)") (class "Default")
      (node (ref "D8") (pin "A") (pinfunction "A_A") (pintype "passive"))
      (node (ref "R19") (pin "1") (pinfunction "1_1") (pintype "passive"))
    )
    (net (code "27") (name "Net-(D9-PadA)") (class "Default")
      (node (ref "D9") (pin "A") (pinfunction "A_A") (pintype "passive"))
      (node (ref "R20") (pin "1") (pinfunction "1_1") (pintype "passive"))
    )
    (net (code "28") (name "Net-(D12-PadA)") (class "Default")
      (node (ref "D12") (pin "A") (pinfunction "A_A") (pintype "passive"))
      (node (ref "U$18") (pin "P$1") (pinfunction "P$1_P$1") (pintype "bidirectional"))
      (node (ref "U$5") (pin "P$3") (pinfunction "P$2_P$3") (pintype "bidirectional"))
      (node (ref "U$5") (pin "P$4") (pinfunction "P$2_P$4") (pintype "bidirectional"))
    )
    (net (code "29") (name "Net-(D12-PadC)") (class "Default")
      (node (ref "D12") (pin "C") (pinfunction "C_C") (pintype "passive"))
      (node (ref "R21") (pin "2") (pinfunction "2_2") (pintype "passive"))
      (node (ref "T4") (pin "B") (pinfunction "B_B") (pintype "passive"))
    )
    (net (code "30") (name "Net-(D13-PadC)") (class "Default")
      (node (ref "D13") (pin "C") (pinfunction "C_C") (pintype "passive"))
      (node (ref "T4") (pin "E") (pinfunction "E_E") (pintype "passive"))
    )
    (net (code "31") (name "Net-(D14-PadA)") (class "Default")
      (node (ref "D14") (pin "A") (pinfunction "A_A") (pintype "passive"))
      (node (ref "U$15") (pin "P$1") (pinfunction "P$1_P$1") (pintype "bidirectional"))
      (node (ref "U$6") (pin "P$3") (pinfunction "P$2_P$3") (pintype "bidirectional"))
      (node (ref "U$6") (pin "P$4") (pinfunction "P$2_P$4") (pintype "bidirectional"))
    )
    (net (code "32") (name "Net-(D14-PadC)") (class "Default")
      (node (ref "D14") (pin "C") (pinfunction "C_C") (pintype "passive"))
      (node (ref "R22") (pin "2") (pinfunction "2_2") (pintype "passive"))
      (node (ref "T5") (pin "B") (pinfunction "B_B") (pintype "passive"))
    )
    (net (code "33") (name "Net-(D15-PadC)") (class "Default")
      (node (ref "D15") (pin "C") (pinfunction "C_C") (pintype "passive"))
      (node (ref "T5") (pin "E") (pinfunction "E_E") (pintype "passive"))
    )
    (net (code "34") (name "Net-(D16-PadA)") (class "Default")
      (node (ref "D16") (pin "A") (pinfunction "A_A") (pintype "passive"))
      (node (ref "U$16") (pin "P$1") (pinfunction "P$1_P$1") (pintype "bidirectional"))
      (node (ref "U$7") (pin "P$3") (pinfunction "P$2_P$3") (pintype "bidirectional"))
      (node (ref "U$7") (pin "P$4") (pinfunction "P$2_P$4") (pintype "bidirectional"))
    )
    (net (code "35") (name "Net-(D16-PadC)") (class "Default")
      (node (ref "D16") (pin "C") (pinfunction "C_C") (pintype "passive"))
      (node (ref "R23") (pin "2") (pinfunction "2_2") (pintype "passive"))
      (node (ref "T6") (pin "B") (pinfunction "B_B") (pintype "passive"))
    )
    (net (code "36") (name "Net-(D17-PadC)") (class "Default")
      (node (ref "D17") (pin "C") (pinfunction "C_C") (pintype "passive"))
      (node (ref "T6") (pin "E") (pinfunction "E_E") (pintype "passive"))
    )
    (net (code "37") (name "Net-(D18-PadA)") (class "Default")
      (node (ref "D18") (pin "A") (pinfunction "A_A") (pintype "passive"))
      (node (ref "U$14") (pin "P$1") (pinfunction "P$1_P$1") (pintype "bidirectional"))
      (node (ref "U$8") (pin "P$3") (pinfunction "P$2_P$3") (pintype "bidirectional"))
      (node (ref "U$8") (pin "P$4") (pinfunction "P$2_P$4") (pintype "bidirectional"))
    )
    (net (code "38") (name "Net-(D18-PadC)") (class "Default")
      (node (ref "D18") (pin "C") (pinfunction "C_C") (pintype "passive"))
      (node (ref "R24") (pin "2") (pinfunction "2_2") (pintype "passive"))
      (node (ref "T7") (pin "B") (pinfunction "B_B") (pintype "passive"))
    )
    (net (code "39") (name "Net-(D19-PadC)") (class "Default")
      (node (ref "D19") (pin "C") (pinfunction "C_C") (pintype "passive"))
      (node (ref "T7") (pin "E") (pinfunction "E_E") (pintype "passive"))
    )
    (net (code "40") (name "Net-(D20-PadA)") (class "Default")
      (node (ref "D20") (pin "A") (pinfunction "A_A") (pintype "passive"))
      (node (ref "U$22") (pin "P$1") (pinfunction "P$1_P$1") (pintype "bidirectional"))
      (node (ref "U$9") (pin "P$3") (pinfunction "P$2_P$3") (pintype "bidirectional"))
      (node (ref "U$9") (pin "P$4") (pinfunction "P$2_P$4") (pintype "bidirectional"))
    )
    (net (code "41") (name "Net-(D20-PadC)") (class "Default")
      (node (ref "D20") (pin "C") (pinfunction "C_C") (pintype "passive"))
      (node (ref "R25") (pin "2") (pinfunction "2_2") (pintype "passive"))
      (node (ref "T8") (pin "B") (pinfunction "B_B") (pintype "passive"))
    )
    (net (code "42") (name "Net-(D21-PadC)") (class "Default")
      (node (ref "D21") (pin "C") (pinfunction "C_C") (pintype "passive"))
      (node (ref "T8") (pin "E") (pinfunction "E_E") (pintype "passive"))
    )
    (net (code "43") (name "Net-(D24-PadA)") (class "Default")
      (node (ref "D24") (pin "A") (pinfunction "A_A") (pintype "passive"))
      (node (ref "U$11") (pin "P$3") (pinfunction "P$2_P$3") (pintype "bidirectional"))
      (node (ref "U$11") (pin "P$4") (pinfunction "P$2_P$4") (pintype "bidirectional"))
      (node (ref "U$20") (pin "P$1") (pinfunction "P$1_P$1") (pintype "bidirectional"))
    )
    (net (code "44") (name "Net-(D24-PadC)") (class "Default")
      (node (ref "D24") (pin "C") (pinfunction "C_C") (pintype "passive"))
      (node (ref "R27") (pin "2") (pinfunction "2_2") (pintype "passive"))
      (node (ref "T10") (pin "B") (pinfunction "B_B") (pintype "passive"))
    )
    (net (code "45") (name "Net-(D25-PadC)") (class "Default")
      (node (ref "D25") (pin "C") (pinfunction "C_C") (pintype "passive"))
      (node (ref "T10") (pin "E") (pinfunction "E_E") (pintype "passive"))
    )
    (net (code "46") (name "Net-(D26-PadA)") (class "Default")
      (node (ref "D26") (pin "A") (pinfunction "A_A") (pintype "passive"))
      (node (ref "U$12") (pin "P$3") (pinfunction "P$2_P$3") (pintype "bidirectional"))
      (node (ref "U$12") (pin "P$4") (pinfunction "P$2_P$4") (pintype "bidirectional"))
      (node (ref "U$21") (pin "P$1") (pinfunction "P$1_P$1") (pintype "bidirectional"))
    )
    (net (code "47") (name "Net-(D26-PadC)") (class "Default")
      (node (ref "D26") (pin "C") (pinfunction "C_C") (pintype "passive"))
      (node (ref "R28") (pin "2") (pinfunction "2_2") (pintype "passive"))
      (node (ref "T11") (pin "B") (pinfunction "B_B") (pintype "passive"))
    )
    (net (code "48") (name "Net-(D27-PadC)") (class "Default")
      (node (ref "D27") (pin "C") (pinfunction "C_C") (pintype "passive"))
      (node (ref "T11") (pin "E") (pinfunction "E_E") (pintype "passive"))
    )
    (net (code "49") (name "Net-(D28-PadA)") (class "Default")
      (node (ref "D28") (pin "A") (pinfunction "A_A") (pintype "passive"))
      (node (ref "U$13") (pin "P$3") (pinfunction "P$2_P$3") (pintype "bidirectional"))
      (node (ref "U$13") (pin "P$4") (pinfunction "P$2_P$4") (pintype "bidirectional"))
      (node (ref "U$19") (pin "P$1") (pinfunction "P$1_P$1") (pintype "bidirectional"))
    )
    (net (code "50") (name "Net-(D28-PadC)") (class "Default")
      (node (ref "D28") (pin "C") (pinfunction "C_C") (pintype "passive"))
      (node (ref "R29") (pin "2") (pinfunction "2_2") (pintype "passive"))
      (node (ref "T12") (pin "B") (pinfunction "B_B") (pintype "passive"))
    )
    (net (code "51") (name "Net-(D29-PadC)") (class "Default")
      (node (ref "D29") (pin "C") (pinfunction "C_C") (pintype "passive"))
      (node (ref "T12") (pin "E") (pinfunction "E_E") (pintype "passive"))
    )
    (net (code "52") (name "Net-(IC1-VOUT)") (class "Default")
      (node (ref "IC1") (pin "3") (pinfunction "VOUT_3") (pintype "output"))
      (node (ref "R3") (pin "1") (pinfunction "1_1") (pintype "passive"))
    )
    (net (code "53") (name "Net-(U$25A-+IN)") (class "Default")
      (node (ref "R10") (pin "2") (pinfunction "2_2") (pintype "passive"))
      (node (ref "R6") (pin "2") (pinfunction "2_2") (pintype "passive"))
      (node (ref "U$25") (pin "3") (pinfunction "+IN_3") (pintype "input"))
    )
    (net (code "54") (name "Net-(U$25A--IN)") (class "Default")
      (node (ref "R4") (pin "1") (pinfunction "1_1") (pintype "passive"))
      (node (ref "R5") (pin "1") (pinfunction "1_1") (pintype "passive"))
      (node (ref "U$25") (pin "2") (pinfunction "-IN_2") (pintype "input"))
    )
    (net (code "55") (name "Net-(U$25B-+IN)") (class "Default")
      (node (ref "R11") (pin "2") (pinfunction "2_2") (pintype "passive"))
      (node (ref "R7") (pin "1") (pinfunction "1_1") (pintype "passive"))
      (node (ref "U$25") (pin "5") (pinfunction "+IN_5") (pintype "input"))
    )
    (net (code "56") (name "Net-(U$25B--IN)") (class "Default")
      (node (ref "R13") (pin "2") (pinfunction "2_2") (pintype "passive"))
      (node (ref "R8") (pin "2") (pinfunction "2_2") (pintype "passive"))
      (node (ref "U$25") (pin "6") (pinfunction "-IN_6") (pintype "input"))
    )
    (net (code "57") (name "unconnected-(IC1-PadIP+1)") (class "Default")
      (node (ref "IC1") (pin "IP+1") (pinfunction "IP+1_IP+1") (pintype "input"))
    )
    (net (code "58") (name "unconnected-(IC1-PadIP-1)") (class "Default")
      (node (ref "IC1") (pin "IP-1") (pinfunction "IP-1_IP-1") (pintype "input"))
    )
  )
)
